# LMP848x_Breakout_v1_4.net
KiCad netlist of a schematic drawn in EAGLE
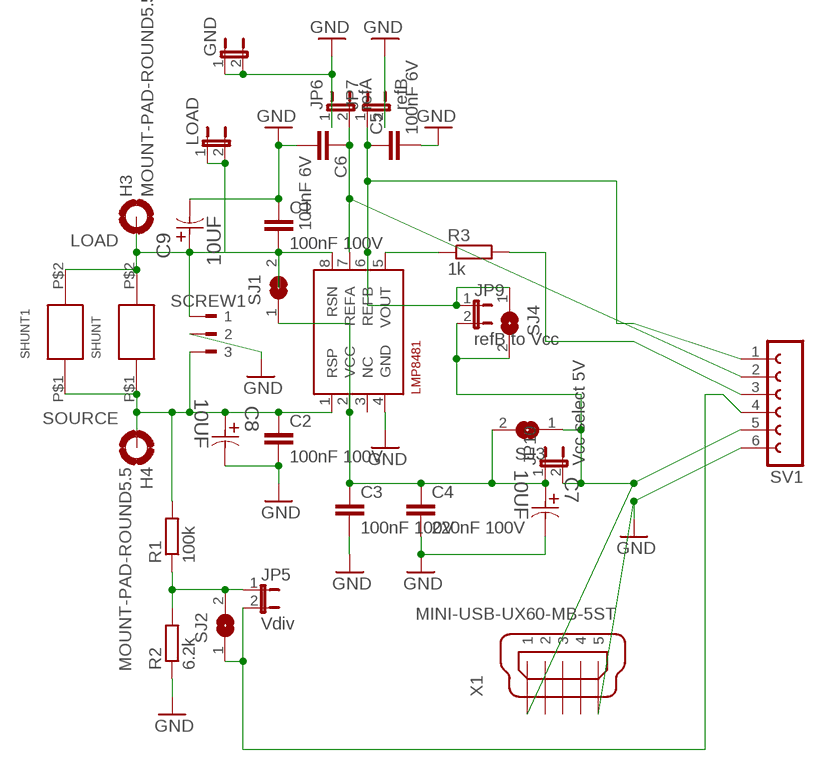
[diagram p0: schematic, sheet 1]

(export (version "E")
  (design (tool "Eeschema 10.0.6"))
  (components
    (comp (ref "C1")
      (value "100nF 100V")
      (footprint "eagle-import:C0805")
      (libsource (lib "eagle-import") (part "C-EUC0805"))
    )
    (comp (ref "C2")
      (value "100nF 100V")
      (footprint "eagle-import:C0805")
      (libsource (lib "eagle-import") (part "C-EUC0805"))
    )
    (comp (ref "C3")
      (value "100nF 100V")
      (footprint "eagle-import:C0805")
      (libsource (lib "eagle-import") (part "C-EUC0805"))
    )
    (comp (ref "C4")
      (value "220nF 100V")
      (footprint "eagle-import:C0805")
      (libsource (lib "eagle-import") (part "C-EUC0805"))
    )
    (comp (ref "C5")
      (value "100nF 6V")
      (footprint "eagle-import:C0805")
      (libsource (lib "eagle-import") (part "C-EUC0805"))
    )
    (comp (ref "C6")
      (value "100nF 6V")
      (footprint "eagle-import:C0805")
      (libsource (lib "eagle-import") (part "C-EUC0805"))
    )
    (comp (ref "C7")
      (value "10UF")
      (footprint "eagle-import:CAPPR250-500X1100")
      (fields (field (name "MPN") "ECA1HM100I") (field (name "TOLERANCE") "±20 %"))
      (libsource (lib "eagle-import") (part "ECA-D5XP2.51HM100I"))
    )
    (comp (ref "C8")
      (value "10UF")
      (footprint "eagle-import:CAPPR250-500X1100")
      (fields (field (name "MPN") "ECA1HM100I") (field (name "TOLERANCE") "±20 %"))
      (libsource (lib "eagle-import") (part "ECA-D5XP2.51HM100I"))
    )
    (comp (ref "C9")
      (value "10UF")
      (footprint "eagle-import:CAPPR250-500X1100")
      (fields (field (name "MPN") "ECA1HM100I") (field (name "TOLERANCE") "±20 %"))
      (libsource (lib "eagle-import") (part "ECA-D5XP2.51HM100I"))
    )
    (comp (ref "GND")
      (value "JP1E")
      (footprint "eagle-import:JP1")
      (libsource (lib "eagle-import") (part "JP1E"))
    )
    (comp (ref "H3")
      (value "MOUNT-PAD-ROUND5.5")
      (footprint "eagle-import:5,5-PAD")
      (libsource (lib "eagle-import") (part "MOUNT-PAD-ROUND5.5"))
    )
    (comp (ref "H4")
      (value "MOUNT-PAD-ROUND5.5")
      (footprint "eagle-import:5,5-PAD")
      (libsource (lib "eagle-import") (part "MOUNT-PAD-ROUND5.5"))
    )
    (comp (ref "JP5")
      (value "Vdiv")
      (footprint "eagle-import:JP1")
      (libsource (lib "eagle-import") (part "JP1E"))
    )
    (comp (ref "JP6")
      (value "refA")
      (footprint "eagle-import:JP1")
      (libsource (lib "eagle-import") (part "JP1E"))
    )
    (comp (ref "JP7")
      (value "refB")
      (footprint "eagle-import:JP1")
      (libsource (lib "eagle-import") (part "JP1E"))
    )
    (comp (ref "JP9")
      (value "refB to Vcc")
      (footprint "eagle-import:JP1")
      (libsource (lib "eagle-import") (part "JP1E"))
    )
    (comp (ref "JP10")
      (value "Vcc select 5V")
      (footprint "eagle-import:JP1")
      (libsource (lib "eagle-import") (part "JP1E"))
    )
    (comp (ref "LMP8481")
      (value "LMP8481-H")
      (footprint "eagle-import:S-PDSO-G08")
      (libsource (lib "eagle-import") (part "LMP8481-H"))
    )
    (comp (ref "LOAD")
      (value "JP1E")
      (footprint "eagle-import:JP1")
      (libsource (lib "eagle-import") (part "JP1E"))
    )
    (comp (ref "R1")
      (value "100k")
      (footprint "eagle-import:0207_7")
      (libsource (lib "eagle-import") (part "R-EU_0207/7"))
    )
    (comp (ref "R2")
      (value "6.2k")
      (footprint "eagle-import:0204_5")
      (libsource (lib "eagle-import") (part "R-EU_0204/5"))
    )
    (comp (ref "R3")
      (value "1k")
      (footprint "eagle-import:0204_5")
      (libsource (lib "eagle-import") (part "R-EU_0204/5"))
    )
    (comp (ref "SCREW1")
      (value "180-3")
      (footprint "eagle-import:180-3")
      (libsource (lib "eagle-import") (part "180-3"))
    )
    (comp (ref "SHUNT")
      (value "EBW_SERIES_15.2MM")
      (footprint "eagle-import:EBW_SERIES_15.2MM")
      (libsource (lib "eagle-import") (part "EBW_SERIES_15.2MM"))
    )
    (comp (ref "SHUNT1")
      (value "EBW_SERIES_15.2MM")
      (footprint "eagle-import:EBW_SERIES_15.2MM")
      (libsource (lib "eagle-import") (part "EBW_SERIES_15.2MM"))
    )
    (comp (ref "SJ1") (value "SJ") (footprint "eagle-import:SJ") (libsource (lib "eagle-import") (part "SJ")))
    (comp (ref "SJ2") (value "SJ") (footprint "eagle-import:SJ") (libsource (lib "eagle-import") (part "SJ")))
    (comp (ref "SJ3") (value "SJ") (footprint "eagle-import:SJ") (libsource (lib "eagle-import") (part "SJ")))
    (comp (ref "SJ4") (value "SJ") (footprint "eagle-import:SJ") (libsource (lib "eagle-import") (part "SJ")))
    (comp (ref "SV1")
      (value "FE06-1")
      (footprint "eagle-import:FE06")
      (libsource (lib "eagle-import") (part "FE06-1"))
    )
    (comp (ref "X1")
      (value "MINI-USB-UX60-MB-5ST")
      (footprint "eagle-import:UX60-MB-5ST")
      (libsource (lib "eagle-import") (part "MINI-USB-UX60-MB-5ST"))
    )
  )
  (nets
    (net (code "1") (name "/LOAD") (class "Default")
      (node (ref "C1") (pin "2") (pinfunction "2_2") (pintype "passive"))
      (node (ref "C9") (pin "1") (pinfunction "1_1") (pintype "passive"))
      (node (ref "H3") (pin "B5,5") (pinfunction "MOUNT_B5,5") (pintype "passive"))
      (node (ref "LMP8481") (pin "8") (pinfunction "RSN_8") (pintype "bidirectional"))
      (node (ref "LOAD") (pin "1") (pinfunction "1_1") (pintype "passive"))
      (node (ref "LOAD") (pin "2") (pinfunction "2_2") (pintype "passive"))
      (node (ref "SCREW1") (pin "1") (pinfunction "1_1") (pintype "passive"))
      (node (ref "SHUNT") (pin "P$2") (pinfunction "P$2_P$2") (pintype "bidirectional"))
      (node (ref "SHUNT1") (pin "P$2") (pinfunction "P$2_P$2") (pintype "bidirectional"))
      (node (ref "SJ1") (pin "2") (pinfunction "2_2") (pintype "passive"))
    )
    (net (code "2") (name "/SOURCE") (class "Default")
      (node (ref "C2") (pin "1") (pinfunction "1_1") (pintype "passive"))
      (node (ref "C8") (pin "1") (pinfunction "1_1") (pintype "passive"))
      (node (ref "H4") (pin "B5,5") (pinfunction "MOUNT_B5,5") (pintype "passive"))
      (node (ref "LMP8481") (pin "1") (pinfunction "RSP_1") (pintype "bidirectional"))
      (node (ref "R1") (pin "2") (pinfunction "2_2") (pintype "passive"))
      (node (ref "SCREW1") (pin "3") (pinfunction "3_3") (pintype "passive"))
      (node (ref "SHUNT") (pin "P$1") (pinfunction "P$1_P$1") (pintype "bidirectional"))
      (node (ref "SHUNT1") (pin "P$1") (pinfunction "P$1_P$1") (pintype "bidirectional"))
    )
    (net (code "3") (name "GND") (class "Default")
      (node (ref "C1") (pin "1") (pinfunction "1_1") (pintype "passive"))
      (node (ref "C2") (pin "2") (pinfunction "2_2") (pintype "passive"))
      (node (ref "C3") (pin "2") (pinfunction "2_2") (pintype "passive"))
      (node (ref "C4") (pin "2") (pinfunction "2_2") (pintype "passive"))
      (node (ref "C5") (pin "2") (pinfunction "2_2") (pintype "passive"))
      (node (ref "C6") (pin "2") (pinfunction "2_2") (pintype "passive"))
      (node (ref "C7") (pin "2") (pinfunction "2_2") (pintype "passive"))
      (node (ref "C8") (pin "2") (pinfunction "2_2") (pintype "passive"))
      (node (ref "C9") (pin "2") (pinfunction "2_2") (pintype "passive"))
      (node (ref "GND") (pin "1") (pinfunction "1_1") (pintype "passive"))
      (node (ref "GND") (pin "2") (pinfunction "2_2") (pintype "passive"))
      (node (ref "JP6") (pin "1") (pinfunction "1_1") (pintype "passive"))
      (node (ref "JP7") (pin "2") (pinfunction "2_2") (pintype "passive"))
      (node (ref "LMP8481") (pin "4") (pinfunction "GND_4") (pintype "bidirectional"))
      (node (ref "R2") (pin "1") (pinfunction "1_1") (pintype "passive"))
      (node (ref "SCREW1") (pin "2") (pinfunction "2_2") (pintype "passive"))
      (node (ref "SV1") (pin "6") (pinfunction "6_6") (pintype "passive"))
      (node (ref "X1") (pin "5") (pinfunction "5_5") (pintype "input"))
    )
    (net (code "4") (name "Net-(JP5-Pad1)") (class "Default")
      (node (ref "JP5") (pin "1") (pinfunction "1_1") (pintype "passive"))
      (node (ref "R1") (pin "1") (pinfunction "1_1") (pintype "passive"))
      (node (ref "R2") (pin "2") (pinfunction "2_2") (pintype "passive"))
      (node (ref "SJ2") (pin "2") (pinfunction "2_2") (pintype "passive"))
    )
    (net (code "5") (name "Net-(JP5-Pad2)") (class "Default")
      (node (ref "JP5") (pin "2") (pinfunction "2_2") (pintype "passive"))
      (node (ref "SJ2") (pin "1") (pinfunction "1_1") (pintype "passive"))
      (node (ref "SV1") (pin "4") (pinfunction "4_4") (pintype "passive"))
    )
    (net (code "6") (name "Net-(JP10-Pad2)") (class "Default")
      (node (ref "JP10") (pin "2") (pinfunction "2_2") (pintype "passive"))
      (node (ref "JP9") (pin "2") (pinfunction "2_2") (pintype "passive"))
      (node (ref "SJ3") (pin "1") (pinfunction "1_1") (pintype "passive"))
      (node (ref "SJ4") (pin "2") (pinfunction "2_2") (pintype "passive"))
      (node (ref "SV1") (pin "5") (pinfunction "5_5") (pintype "passive"))
      (node (ref "X1") (pin "1") (pinfunction "1_1") (pintype "input"))
    )
    (net (code "7") (name "Net-(LMP8481-REFA)") (class "Default")
      (node (ref "C6") (pin "1") (pinfunction "1_1") (pintype "passive"))
      (node (ref "JP6") (pin "2") (pinfunction "2_2") (pintype "passive"))
      (node (ref "LMP8481") (pin "7") (pinfunction "REFA_7") (pintype "bidirectional"))
      (node (ref "SV1") (pin "2") (pinfunction "2_2") (pintype "passive"))
    )
    (net (code "8") (name "Net-(LMP8481-REFB)") (class "Default")
      (node (ref "C5") (pin "1") (pinfunction "1_1") (pintype "passive"))
      (node (ref "JP7") (pin "1") (pinfunction "1_1") (pintype "passive"))
      (node (ref "JP9") (pin "1") (pinfunction "1_1") (pintype "passive"))
      (node (ref "LMP8481") (pin "6") (pinfunction "REFB_6") (pintype "bidirectional"))
      (node (ref "SJ4") (pin "1") (pinfunction "1_1") (pintype "passive"))
      (node (ref "SV1") (pin "1") (pinfunction "1_1") (pintype "passive"))
    )
    (net (code "9") (name "Net-(LMP8481-VCC)") (class "Default")
      (node (ref "C3") (pin "1") (pinfunction "1_1") (pintype "passive"))
      (node (ref "C4") (pin "1") (pinfunction "1_1") (pintype "passive"))
      (node (ref "C7") (pin "1") (pinfunction "1_1") (pintype "passive"))
      (node (ref "JP10") (pin "1") (pinfunction "1_1") (pintype "passive"))
      (node (ref "LMP8481") (pin "2") (pinfunction "VCC_2") (pintype "bidirectional"))
      (node (ref "SJ1") (pin "1") (pinfunction "1_1") (pintype "passive"))
      (node (ref "SJ3") (pin "2") (pinfunction "2_2") (pintype "passive"))
    )
    (net (code "10") (name "Net-(LMP8481-VOUT)") (class "Default")
      (node (ref "LMP8481") (pin "5") (pinfunction "VOUT_5") (pintype "bidirectional"))
      (node (ref "R3") (pin "1") (pinfunction "1_1") (pintype "passive"))
    )
    (net (code "11") (name "Net-(R3-Pad2)") (class "Default")
      (node (ref "R3") (pin "2") (pinfunction "2_2") (pintype "passive"))
      (node (ref "SV1") (pin "3") (pinfunction "3_3") (pintype "passive"))
    )
    (net (code "12") (name "unconnected-(LMP8481-NC-Pad3)") (class "Default")
      (node (ref "LMP8481") (pin "3") (pinfunction "NC_3") (pintype "bidirectional"))
    )
    (net (code "13") (name "unconnected-(X1-Pad2)") (class "Default")
      (node (ref "X1") (pin "2") (pinfunction "2_2") (pintype "input"))
    )
    (net (code "14") (name "unconnected-(X1-Pad3)") (class "Default")
      (node (ref "X1") (pin "3") (pinfunction "3_3") (pintype "input"))
    )
    (net (code "15") (name "unconnected-(X1-Pad4)") (class "Default")
      (node (ref "X1") (pin "4") (pinfunction "4_4") (pintype "input"))
    )
  )
)
